# ioboard.net
KiCad netlist of a schematic drawn in EAGLE
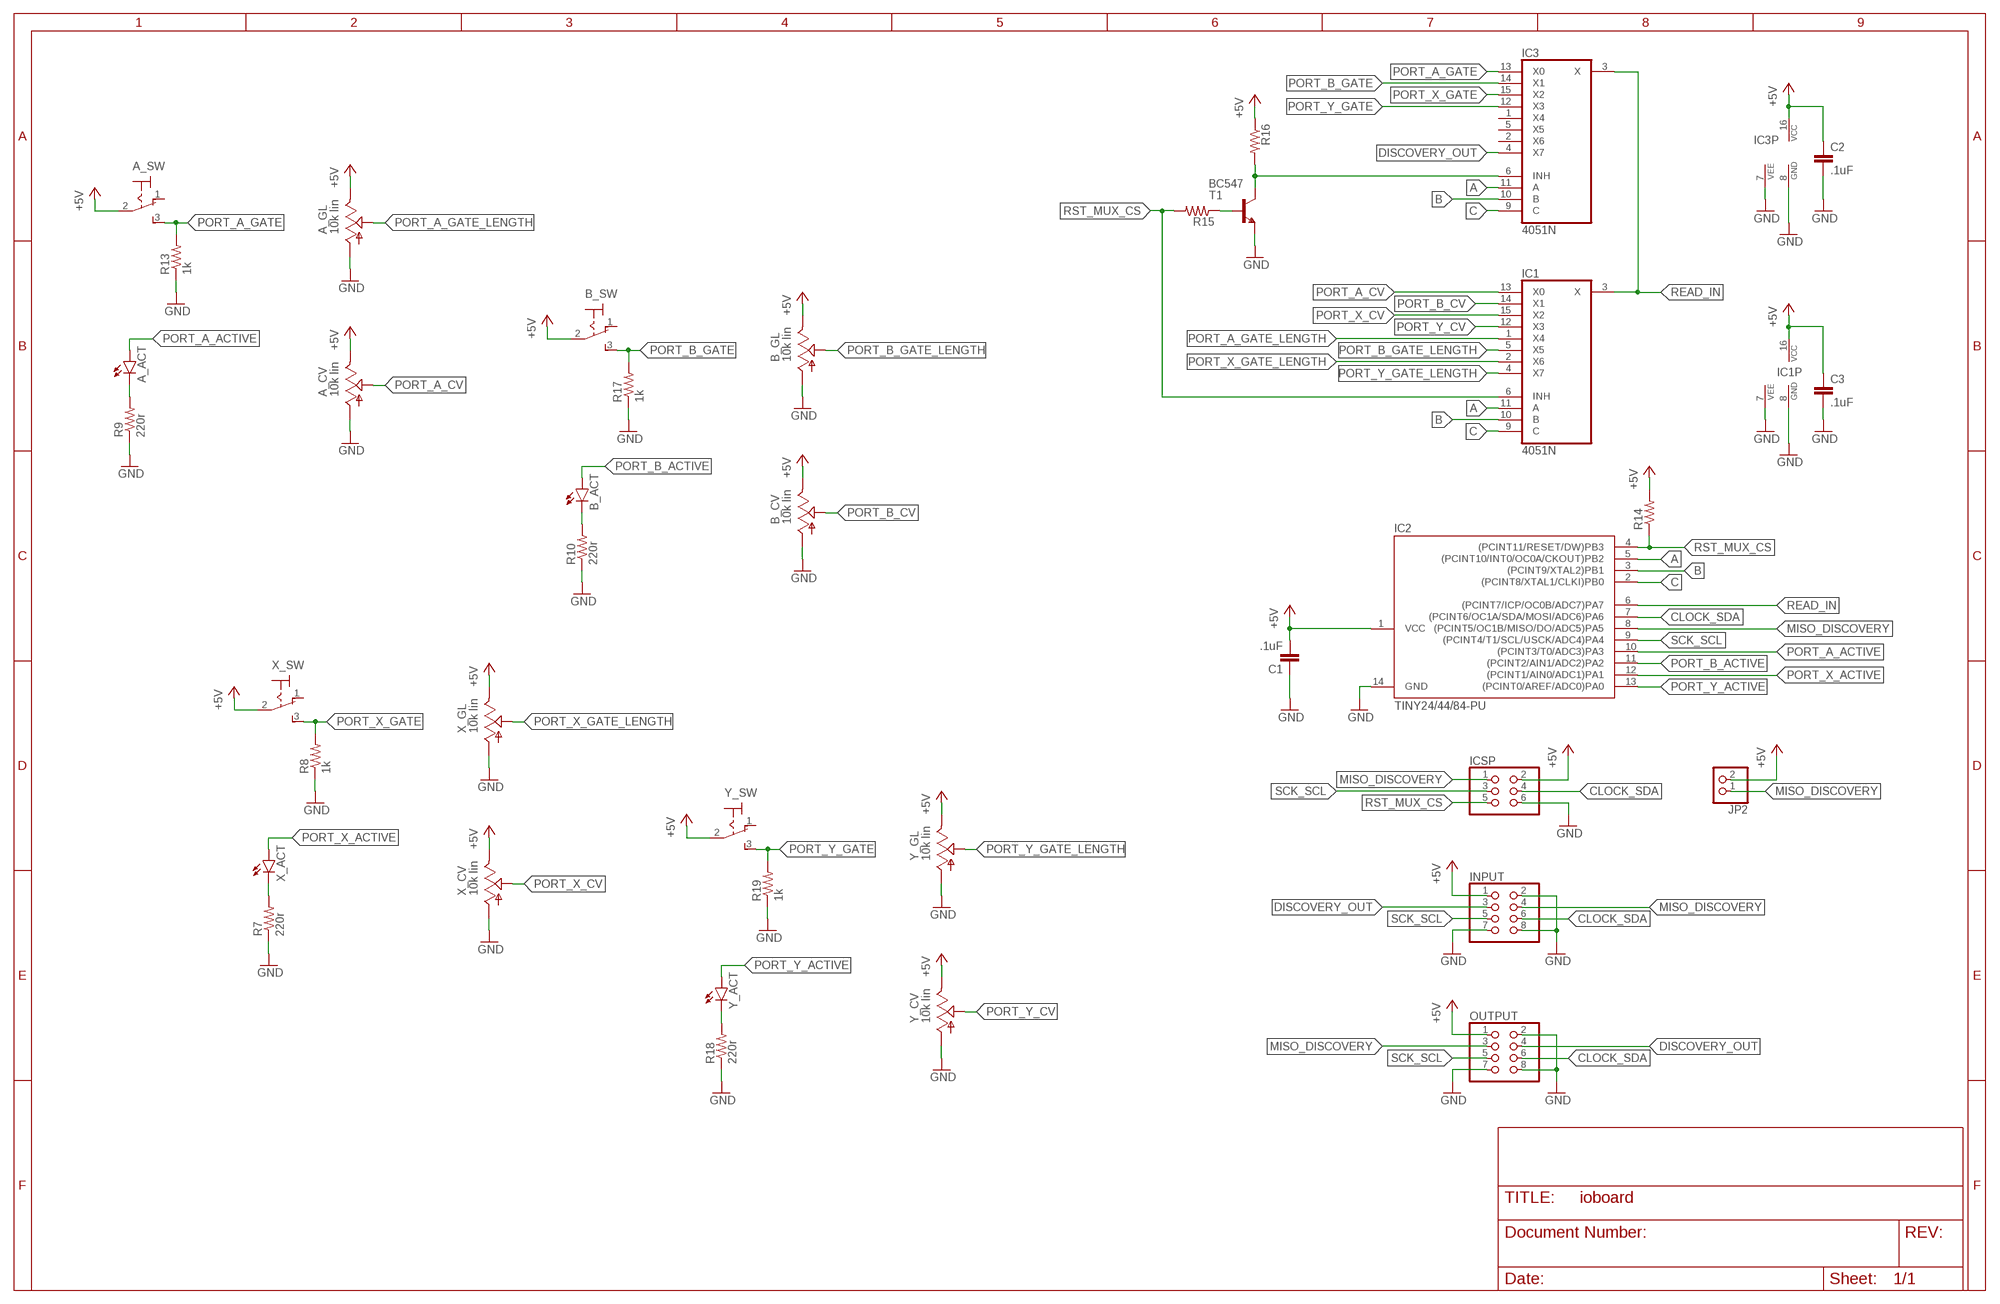
[diagram p0: schematic, sheet 1]

(export (version "E")
  (design (tool "Eeschema 10.0.6"))
  (components
    (comp (ref "A_ACT")
      (value "LED5MM")
      (footprint "eagle-import:LED5MM")
      (libsource (lib "eagle-import") (part "LED5MM"))
    )
    (comp (ref "A_CV")
      (value "10k lin")
      (footprint "eagle-import:EVUF")
      (libsource (lib "eagle-import") (part "ALPHA-9MMA"))
    )
    (comp (ref "A_GL")
      (value "10k lin")
      (footprint "eagle-import:EVUF")
      (libsource (lib "eagle-import") (part "ALPHA-9MMA"))
    )
    (comp (ref "A_SW")
      (value "M9040P")
      (footprint "eagle-import:M9040P")
      (libsource (lib "eagle-import") (part "M9040P"))
    )
    (comp (ref "B_ACT")
      (value "LED5MM")
      (footprint "eagle-import:LED5MM")
      (libsource (lib "eagle-import") (part "LED5MM"))
    )
    (comp (ref "B_CV")
      (value "10k lin")
      (footprint "eagle-import:EVUF")
      (libsource (lib "eagle-import") (part "ALPHA-9MMA"))
    )
    (comp (ref "B_GL")
      (value "10k lin")
      (footprint "eagle-import:EVUF")
      (libsource (lib "eagle-import") (part "ALPHA-9MMA"))
    )
    (comp (ref "B_SW")
      (value "M9040P")
      (footprint "eagle-import:M9040P")
      (libsource (lib "eagle-import") (part "M9040P"))
    )
    (comp (ref "C1")
      (value ".1uF")
      (footprint "eagle-import:C050-024X044")
      (libsource (lib "eagle-import") (part "C-EU050-024X044"))
    )
    (comp (ref "C2")
      (value ".1uF")
      (footprint "eagle-import:C050-024X044")
      (libsource (lib "eagle-import") (part "C-EU050-024X044"))
    )
    (comp (ref "C3")
      (value ".1uF")
      (footprint "eagle-import:C050-024X044")
      (libsource (lib "eagle-import") (part "C-EU050-024X044"))
    )
    (comp (ref "IC1")
      (value "4051N")
      (footprint "eagle-import:DIL16")
      (libsource (lib "eagle-import") (part "4051N"))
    )
    (comp (ref "IC2")
      (value "TINY24/44/84-PU")
      (footprint "eagle-import:DIL14")
      (libsource (lib "eagle-import") (part "TINY24/44/84-PU"))
    )
    (comp (ref "IC3")
      (value "4051N")
      (footprint "eagle-import:DIL16")
      (libsource (lib "eagle-import") (part "4051N"))
    )
    (comp (ref "ICSP")
      (value "PINHD-2X3")
      (footprint "eagle-import:2X03")
      (libsource (lib "eagle-import") (part "PINHD-2X3"))
    )
    (comp (ref "INPUT")
      (value "PINHD-2X4")
      (footprint "eagle-import:2X04")
      (libsource (lib "eagle-import") (part "PINHD-2X4"))
    )
    (comp (ref "JP2")
      (value "PINHD-1X2")
      (footprint "eagle-import:1X02")
      (libsource (lib "eagle-import") (part "PINHD-1X2"))
    )
    (comp (ref "OUTPUT")
      (value "PINHD-2X4")
      (footprint "eagle-import:2X04")
      (libsource (lib "eagle-import") (part "PINHD-2X4"))
    )
    (comp (ref "R7")
      (value "220r")
      (footprint "eagle-import:0204_7")
      (libsource (lib "eagle-import") (part "R-US_0204/7"))
    )
    (comp (ref "R8")
      (value "1k")
      (footprint "eagle-import:0204_7")
      (libsource (lib "eagle-import") (part "R-US_0204/7"))
    )
    (comp (ref "R9")
      (value "220r")
      (footprint "eagle-import:0204_7")
      (libsource (lib "eagle-import") (part "R-US_0204/7"))
    )
    (comp (ref "R10")
      (value "220r")
      (footprint "eagle-import:0204_7")
      (libsource (lib "eagle-import") (part "R-US_0204/7"))
    )
    (comp (ref "R13")
      (value "1k")
      (footprint "eagle-import:0204_7")
      (libsource (lib "eagle-import") (part "R-US_0204/7"))
    )
    (comp (ref "R14")
      (value "R-US_0204/7")
      (footprint "eagle-import:0204_7")
      (libsource (lib "eagle-import") (part "R-US_0204/7"))
    )
    (comp (ref "R15")
      (value "R-US_0204/7")
      (footprint "eagle-import:0204_7")
      (libsource (lib "eagle-import") (part "R-US_0204/7"))
    )
    (comp (ref "R16")
      (value "R-US_0204/7")
      (footprint "eagle-import:0204_7")
      (libsource (lib "eagle-import") (part "R-US_0204/7"))
    )
    (comp (ref "R17")
      (value "1k")
      (footprint "eagle-import:0204_7")
      (libsource (lib "eagle-import") (part "R-US_0204/7"))
    )
    (comp (ref "R18")
      (value "220r")
      (footprint "eagle-import:0204_7")
      (libsource (lib "eagle-import") (part "R-US_0204/7"))
    )
    (comp (ref "R19")
      (value "1k")
      (footprint "eagle-import:0204_7")
      (libsource (lib "eagle-import") (part "R-US_0204/7"))
    )
    (comp (ref "T1")
      (value "BC547")
      (footprint "eagle-import:TO92")
      (libsource (lib "eagle-import") (part "BC547"))
    )
    (comp (ref "X_ACT")
      (value "LED5MM")
      (footprint "eagle-import:LED5MM")
      (libsource (lib "eagle-import") (part "LED5MM"))
    )
    (comp (ref "X_CV")
      (value "10k lin")
      (footprint "eagle-import:EVUF")
      (libsource (lib "eagle-import") (part "ALPHA-9MMA"))
    )
    (comp (ref "X_GL")
      (value "10k lin")
      (footprint "eagle-import:EVUF")
      (libsource (lib "eagle-import") (part "ALPHA-9MMA"))
    )
    (comp (ref "X_SW")
      (value "M9040P")
      (footprint "eagle-import:M9040P")
      (libsource (lib "eagle-import") (part "M9040P"))
    )
    (comp (ref "Y_ACT")
      (value "LED5MM")
      (footprint "eagle-import:LED5MM")
      (libsource (lib "eagle-import") (part "LED5MM"))
    )
    (comp (ref "Y_CV")
      (value "10k lin")
      (footprint "eagle-import:EVUF")
      (libsource (lib "eagle-import") (part "ALPHA-9MMA"))
    )
    (comp (ref "Y_GL")
      (value "10k lin")
      (footprint "eagle-import:EVUF")
      (libsource (lib "eagle-import") (part "ALPHA-9MMA"))
    )
    (comp (ref "Y_SW")
      (value "M9040P")
      (footprint "eagle-import:M9040P")
      (libsource (lib "eagle-import") (part "M9040P"))
    )
  )
  (nets
    (net (code "1") (name "+5V") (class "Default")
      (node (ref "A_CV") (pin "3") (pinfunction "E_3") (pintype "passive"))
      (node (ref "A_GL") (pin "3") (pinfunction "E_3") (pintype "passive"))
      (node (ref "A_SW") (pin "2") (pinfunction "P_2") (pintype "passive"))
      (node (ref "B_CV") (pin "3") (pinfunction "E_3") (pintype "passive"))
      (node (ref "B_GL") (pin "3") (pinfunction "E_3") (pintype "passive"))
      (node (ref "B_SW") (pin "2") (pinfunction "P_2") (pintype "passive"))
      (node (ref "C1") (pin "2") (pinfunction "2_2") (pintype "passive"))
      (node (ref "C2") (pin "1") (pinfunction "1_1") (pintype "passive"))
      (node (ref "C3") (pin "1") (pinfunction "1_1") (pintype "passive"))
      (node (ref "IC1") (pin "16") (pinfunction "VCC_16") (pintype "power_in"))
      (node (ref "IC2") (pin "1") (pinfunction "VCC_1") (pintype "power_in"))
      (node (ref "IC3") (pin "16") (pinfunction "VCC_16") (pintype "power_in"))
      (node (ref "ICSP") (pin "2") (pinfunction "2_2") (pintype "passive"))
      (node (ref "INPUT") (pin "1") (pinfunction "1_1") (pintype "passive"))
      (node (ref "JP2") (pin "2") (pinfunction "2_2") (pintype "passive"))
      (node (ref "OUTPUT") (pin "1") (pinfunction "1_1") (pintype "passive"))
      (node (ref "R14") (pin "2") (pinfunction "2_2") (pintype "passive"))
      (node (ref "R16") (pin "1") (pinfunction "1_1") (pintype "passive"))
      (node (ref "X_CV") (pin "3") (pinfunction "E_3") (pintype "passive"))
      (node (ref "X_GL") (pin "3") (pinfunction "E_3") (pintype "passive"))
      (node (ref "X_SW") (pin "2") (pinfunction "P_2") (pintype "passive"))
      (node (ref "Y_CV") (pin "3") (pinfunction "E_3") (pintype "passive"))
      (node (ref "Y_GL") (pin "3") (pinfunction "E_3") (pintype "passive"))
      (node (ref "Y_SW") (pin "2") (pinfunction "P_2") (pintype "passive"))
    )
    (net (code "2") (name "A") (class "Default")
      (node (ref "IC1") (pin "11") (pinfunction "A_11") (pintype "input"))
      (node (ref "IC2") (pin "5") (pinfunction "(PCINT10/INT0/OC0A/CKOUT)PB2_5") (pintype "bidirectional"))
      (node (ref "IC3") (pin "11") (pinfunction "A_11") (pintype "input"))
    )
    (net (code "3") (name "B") (class "Default")
      (node (ref "IC1") (pin "10") (pinfunction "B_10") (pintype "input"))
      (node (ref "IC2") (pin "3") (pinfunction "(PCINT9/XTAL2)PB1_3") (pintype "bidirectional"))
      (node (ref "IC3") (pin "10") (pinfunction "B_10") (pintype "input"))
    )
    (net (code "4") (name "C") (class "Default")
      (node (ref "IC1") (pin "9") (pinfunction "C_9") (pintype "input"))
      (node (ref "IC2") (pin "2") (pinfunction "(PCINT8/XTAL1/CLKI)PB0_2") (pintype "bidirectional"))
      (node (ref "IC3") (pin "9") (pinfunction "C_9") (pintype "input"))
    )
    (net (code "5") (name "CLOCK_SDA") (class "Default")
      (node (ref "IC2") (pin "7") (pinfunction "(PCINT6/OC1A/SDA/MOSI/ADC6)PA6_7") (pintype "bidirectional"))
      (node (ref "ICSP") (pin "4") (pinfunction "4_4") (pintype "passive"))
      (node (ref "INPUT") (pin "6") (pinfunction "6_6") (pintype "passive"))
      (node (ref "OUTPUT") (pin "6") (pinfunction "6_6") (pintype "passive"))
    )
    (net (code "6") (name "DISCOVERY_OUT") (class "Default")
      (node (ref "IC3") (pin "4") (pinfunction "X7_4") (pintype "bidirectional"))
      (node (ref "INPUT") (pin "3") (pinfunction "3_3") (pintype "passive"))
      (node (ref "OUTPUT") (pin "4") (pinfunction "4_4") (pintype "passive"))
    )
    (net (code "7") (name "GND") (class "Default")
      (node (ref "A_CV") (pin "1") (pinfunction "A_1") (pintype "passive"))
      (node (ref "A_GL") (pin "1") (pinfunction "A_1") (pintype "passive"))
      (node (ref "B_CV") (pin "1") (pinfunction "A_1") (pintype "passive"))
      (node (ref "B_GL") (pin "1") (pinfunction "A_1") (pintype "passive"))
      (node (ref "C1") (pin "1") (pinfunction "1_1") (pintype "passive"))
      (node (ref "C2") (pin "2") (pinfunction "2_2") (pintype "passive"))
      (node (ref "C3") (pin "2") (pinfunction "2_2") (pintype "passive"))
      (node (ref "IC1") (pin "7") (pinfunction "VEE_7") (pintype "power_in"))
      (node (ref "IC1") (pin "8") (pinfunction "GND_8") (pintype "power_in"))
      (node (ref "IC2") (pin "14") (pinfunction "GND_14") (pintype "power_in"))
      (node (ref "IC3") (pin "7") (pinfunction "VEE_7") (pintype "power_in"))
      (node (ref "IC3") (pin "8") (pinfunction "GND_8") (pintype "power_in"))
      (node (ref "ICSP") (pin "6") (pinfunction "6_6") (pintype "passive"))
      (node (ref "INPUT") (pin "2") (pinfunction "2_2") (pintype "passive"))
      (node (ref "INPUT") (pin "7") (pinfunction "7_7") (pintype "passive"))
      (node (ref "INPUT") (pin "8") (pinfunction "8_8") (pintype "passive"))
      (node (ref "OUTPUT") (pin "2") (pinfunction "2_2") (pintype "passive"))
      (node (ref "OUTPUT") (pin "7") (pinfunction "7_7") (pintype "passive"))
      (node (ref "OUTPUT") (pin "8") (pinfunction "8_8") (pintype "passive"))
      (node (ref "R10") (pin "1") (pinfunction "1_1") (pintype "passive"))
      (node (ref "R13") (pin "1") (pinfunction "1_1") (pintype "passive"))
      (node (ref "R17") (pin "1") (pinfunction "1_1") (pintype "passive"))
      (node (ref "R18") (pin "1") (pinfunction "1_1") (pintype "passive"))
      (node (ref "R19") (pin "1") (pinfunction "1_1") (pintype "passive"))
      (node (ref "R7") (pin "1") (pinfunction "1_1") (pintype "passive"))
      (node (ref "R8") (pin "1") (pinfunction "1_1") (pintype "passive"))
      (node (ref "R9") (pin "1") (pinfunction "1_1") (pintype "passive"))
      (node (ref "T1") (pin "1") (pinfunction "E_1") (pintype "passive"))
      (node (ref "X_CV") (pin "1") (pinfunction "A_1") (pintype "passive"))
      (node (ref "X_GL") (pin "1") (pinfunction "A_1") (pintype "passive"))
      (node (ref "Y_CV") (pin "1") (pinfunction "A_1") (pintype "passive"))
      (node (ref "Y_GL") (pin "1") (pinfunction "A_1") (pintype "passive"))
    )
    (net (code "8") (name "MISO_DISCOVERY") (class "Default")
      (node (ref "IC2") (pin "8") (pinfunction "(PCINT5/OC1B/MISO/DO/ADC5)PA5_8") (pintype "bidirectional"))
      (node (ref "ICSP") (pin "1") (pinfunction "1_1") (pintype "passive"))
      (node (ref "INPUT") (pin "4") (pinfunction "4_4") (pintype "passive"))
      (node (ref "JP2") (pin "1") (pinfunction "1_1") (pintype "passive"))
      (node (ref "OUTPUT") (pin "3") (pinfunction "3_3") (pintype "passive"))
    )
    (net (code "9") (name "Net-(A_ACT-C)") (class "Default")
      (node (ref "A_ACT") (pin "K") (pinfunction "C_K") (pintype "passive"))
      (node (ref "R9") (pin "2") (pinfunction "2_2") (pintype "passive"))
    )
    (net (code "10") (name "Net-(B_ACT-C)") (class "Default")
      (node (ref "B_ACT") (pin "K") (pinfunction "C_K") (pintype "passive"))
      (node (ref "R10") (pin "2") (pinfunction "2_2") (pintype "passive"))
    )
    (net (code "11") (name "Net-(IC3A-INH)") (class "Default")
      (node (ref "IC3") (pin "6") (pinfunction "INH_6") (pintype "input"))
      (node (ref "R16") (pin "2") (pinfunction "2_2") (pintype "passive"))
      (node (ref "T1") (pin "3") (pinfunction "C_3") (pintype "passive"))
    )
    (net (code "12") (name "Net-(T1-B)") (class "Default")
      (node (ref "R15") (pin "1") (pinfunction "1_1") (pintype "passive"))
      (node (ref "T1") (pin "2") (pinfunction "B_2") (pintype "passive"))
    )
    (net (code "13") (name "Net-(X_ACT-C)") (class "Default")
      (node (ref "R7") (pin "2") (pinfunction "2_2") (pintype "passive"))
      (node (ref "X_ACT") (pin "K") (pinfunction "C_K") (pintype "passive"))
    )
    (net (code "14") (name "Net-(Y_ACT-C)") (class "Default")
      (node (ref "R18") (pin "2") (pinfunction "2_2") (pintype "passive"))
      (node (ref "Y_ACT") (pin "K") (pinfunction "C_K") (pintype "passive"))
    )
    (net (code "15") (name "PORT_A_ACTIVE") (class "Default")
      (node (ref "A_ACT") (pin "A") (pinfunction "A_A") (pintype "passive"))
      (node (ref "IC2") (pin "10") (pinfunction "(PCINT3/T0/ADC3)PA3_10") (pintype "bidirectional"))
    )
    (net (code "16") (name "PORT_A_CV") (class "Default")
      (node (ref "A_CV") (pin "2") (pinfunction "S_2") (pintype "passive"))
      (node (ref "IC1") (pin "13") (pinfunction "X0_13") (pintype "bidirectional"))
    )
    (net (code "17") (name "PORT_A_GATE") (class "Default")
      (node (ref "A_SW") (pin "3") (pinfunction "S_3") (pintype "passive"))
      (node (ref "IC3") (pin "13") (pinfunction "X0_13") (pintype "bidirectional"))
      (node (ref "R13") (pin "2") (pinfunction "2_2") (pintype "passive"))
    )
    (net (code "18") (name "PORT_A_GATE_LENGTH") (class "Default")
      (node (ref "A_GL") (pin "2") (pinfunction "S_2") (pintype "passive"))
      (node (ref "IC1") (pin "1") (pinfunction "X4_1") (pintype "bidirectional"))
    )
    (net (code "19") (name "PORT_B_ACTIVE") (class "Default")
      (node (ref "B_ACT") (pin "A") (pinfunction "A_A") (pintype "passive"))
      (node (ref "IC2") (pin "11") (pinfunction "(PCINT2/AIN1/ADC2)PA2_11") (pintype "bidirectional"))
    )
    (net (code "20") (name "PORT_B_CV") (class "Default")
      (node (ref "B_CV") (pin "2") (pinfunction "S_2") (pintype "passive"))
      (node (ref "IC1") (pin "14") (pinfunction "X1_14") (pintype "bidirectional"))
    )
    (net (code "21") (name "PORT_B_GATE") (class "Default")
      (node (ref "B_SW") (pin "3") (pinfunction "S_3") (pintype "passive"))
      (node (ref "IC3") (pin "14") (pinfunction "X1_14") (pintype "bidirectional"))
      (node (ref "R17") (pin "2") (pinfunction "2_2") (pintype "passive"))
    )
    (net (code "22") (name "PORT_B_GATE_LENGTH") (class "Default")
      (node (ref "B_GL") (pin "2") (pinfunction "S_2") (pintype "passive"))
      (node (ref "IC1") (pin "5") (pinfunction "X5_5") (pintype "bidirectional"))
    )
    (net (code "23") (name "PORT_X_ACTIVE") (class "Default")
      (node (ref "IC2") (pin "12") (pinfunction "(PCINT1/AIN0/ADC1)PA1_12") (pintype "bidirectional"))
      (node (ref "X_ACT") (pin "A") (pinfunction "A_A") (pintype "passive"))
    )
    (net (code "24") (name "PORT_X_CV") (class "Default")
      (node (ref "IC1") (pin "15") (pinfunction "X2_15") (pintype "bidirectional"))
      (node (ref "X_CV") (pin "2") (pinfunction "S_2") (pintype "passive"))
    )
    (net (code "25") (name "PORT_X_GATE") (class "Default")
      (node (ref "IC3") (pin "15") (pinfunction "X2_15") (pintype "bidirectional"))
      (node (ref "R8") (pin "2") (pinfunction "2_2") (pintype "passive"))
      (node (ref "X_SW") (pin "3") (pinfunction "S_3") (pintype "passive"))
    )
    (net (code "26") (name "PORT_X_GATE_LENGTH") (class "Default")
      (node (ref "IC1") (pin "2") (pinfunction "X6_2") (pintype "bidirectional"))
      (node (ref "X_GL") (pin "2") (pinfunction "S_2") (pintype "passive"))
    )
    (net (code "27") (name "PORT_Y_ACTIVE") (class "Default")
      (node (ref "IC2") (pin "13") (pinfunction "(PCINT0/AREF/ADC0)PA0_13") (pintype "bidirectional"))
      (node (ref "Y_ACT") (pin "A") (pinfunction "A_A") (pintype "passive"))
    )
    (net (code "28") (name "PORT_Y_CV") (class "Default")
      (node (ref "IC1") (pin "12") (pinfunction "X3_12") (pintype "bidirectional"))
      (node (ref "Y_CV") (pin "2") (pinfunction "S_2") (pintype "passive"))
    )
    (net (code "29") (name "PORT_Y_GATE") (class "Default")
      (node (ref "IC3") (pin "12") (pinfunction "X3_12") (pintype "bidirectional"))
      (node (ref "R19") (pin "2") (pinfunction "2_2") (pintype "passive"))
      (node (ref "Y_SW") (pin "3") (pinfunction "S_3") (pintype "passive"))
    )
    (net (code "30") (name "PORT_Y_GATE_LENGTH") (class "Default")
      (node (ref "IC1") (pin "4") (pinfunction "X7_4") (pintype "bidirectional"))
      (node (ref "Y_GL") (pin "2") (pinfunction "S_2") (pintype "passive"))
    )
    (net (code "31") (name "READ_IN") (class "Default")
      (node (ref "IC1") (pin "3") (pinfunction "X_3") (pintype "bidirectional"))
      (node (ref "IC2") (pin "6") (pinfunction "(PCINT7/ICP/OC0B/ADC7)PA7_6") (pintype "bidirectional"))
      (node (ref "IC3") (pin "3") (pinfunction "X_3") (pintype "bidirectional"))
    )
    (net (code "32") (name "RST_MUX_CS") (class "Default")
      (node (ref "IC1") (pin "6") (pinfunction "INH_6") (pintype "input"))
      (node (ref "IC2") (pin "4") (pinfunction "(PCINT11/RESET/DW)PB3_4") (pintype "bidirectional"))
      (node (ref "ICSP") (pin "5") (pinfunction "5_5") (pintype "passive"))
      (node (ref "R14") (pin "1") (pinfunction "1_1") (pintype "passive"))
      (node (ref "R15") (pin "2") (pinfunction "2_2") (pintype "passive"))
    )
    (net (code "33") (name "SCK_SCL") (class "Default")
      (node (ref "IC2") (pin "9") (pinfunction "(PCINT4/T1/SCL/USCK/ADC4)PA4_9") (pintype "bidirectional"))
      (node (ref "ICSP") (pin "3") (pinfunction "3_3") (pintype "passive"))
      (node (ref "INPUT") (pin "5") (pinfunction "5_5") (pintype "passive"))
      (node (ref "OUTPUT") (pin "5") (pinfunction "5_5") (pintype "passive"))
    )
    (net (code "34") (name "unconnected-(A_SW-O-Pad1)") (class "Default")
      (node (ref "A_SW") (pin "1") (pinfunction "O_1") (pintype "passive"))
    )
    (net (code "35") (name "unconnected-(B_SW-O-Pad1)") (class "Default")
      (node (ref "B_SW") (pin "1") (pinfunction "O_1") (pintype "passive"))
    )
    (net (code "36") (name "unconnected-(IC3A-X4-Pad1)") (class "Default")
      (node (ref "IC3") (pin "1") (pinfunction "X4_1") (pintype "bidirectional"))
    )
    (net (code "37") (name "unconnected-(IC3A-X5-Pad5)") (class "Default")
      (node (ref "IC3") (pin "5") (pinfunction "X5_5") (pintype "bidirectional"))
    )
    (net (code "38") (name "unconnected-(IC3A-X6-Pad2)") (class "Default")
      (node (ref "IC3") (pin "2") (pinfunction "X6_2") (pintype "bidirectional"))
    )
    (net (code "39") (name "unconnected-(X_SW-O-Pad1)") (class "Default")
      (node (ref "X_SW") (pin "1") (pinfunction "O_1") (pintype "passive"))
    )
    (net (code "40") (name "unconnected-(Y_SW-O-Pad1)") (class "Default")
      (node (ref "Y_SW") (pin "1") (pinfunction "O_1") (pintype "passive"))
    )
  )
)
